# common_board_smd.net
KiCad netlist of a schematic drawn in EAGLE
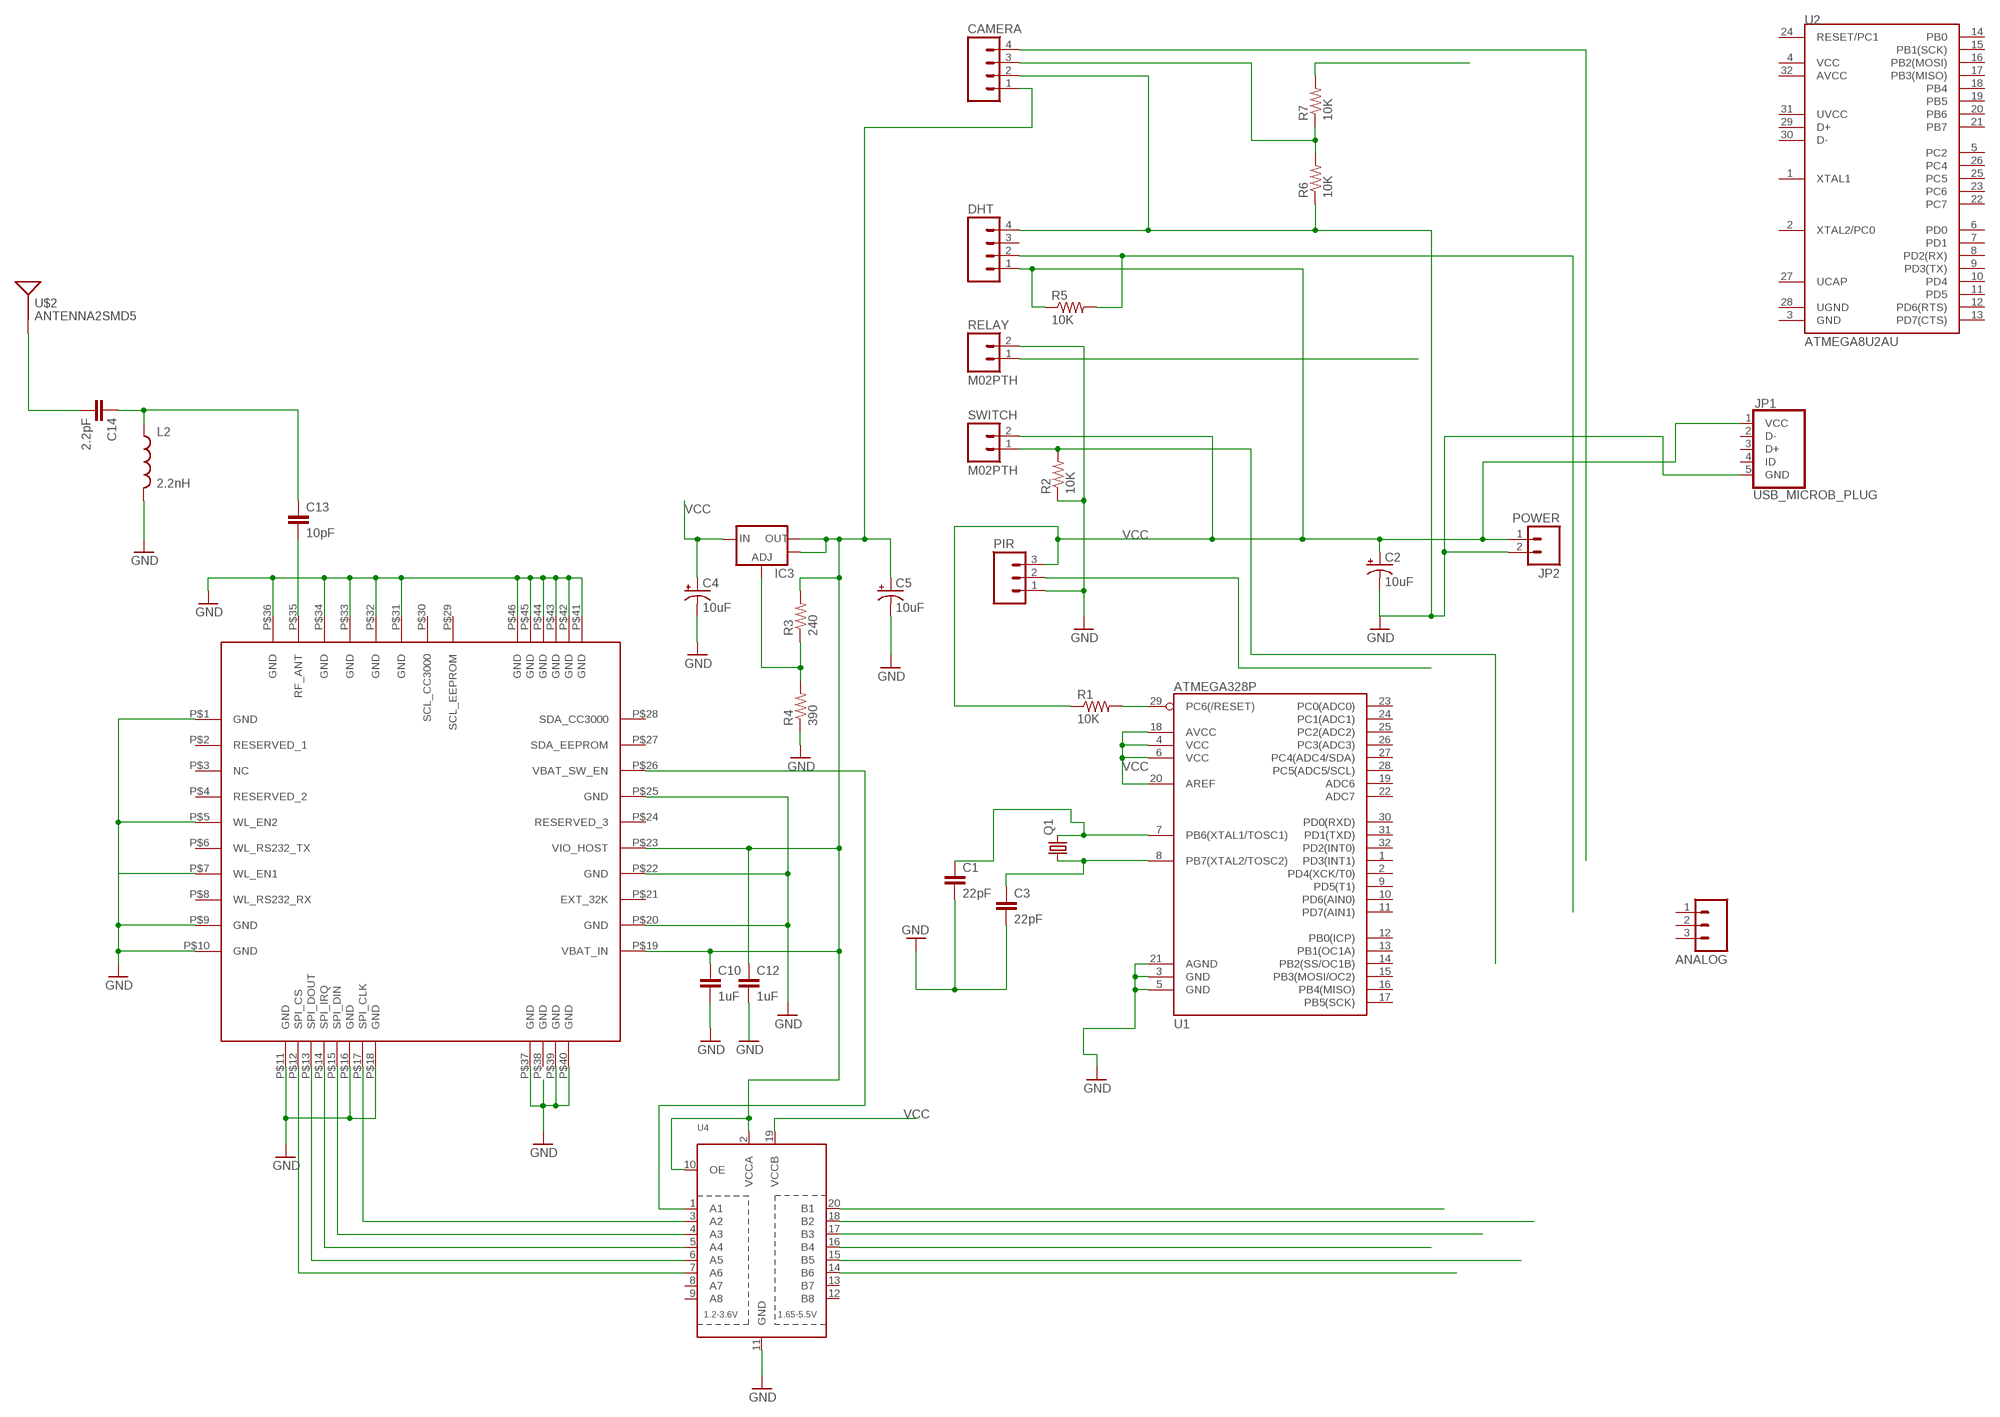
[diagram p0: schematic, sheet 1]

(export (version "E")
  (design (tool "Eeschema 10.0.6"))
  (components
    (comp (ref "ANALOG")
      (value "M03PTH")
      (footprint "eagle-import:1X03")
      (libsource (lib "eagle-import") (part "M03PTH"))
    )
    (comp (ref "C1")
      (value "22pF")
      (footprint "eagle-import:0805")
      (libsource (lib "eagle-import") (part "SparkFun-Passives_CAP0805"))
    )
    (comp (ref "C2")
      (value "10uF")
      (footprint "eagle-import:EIA3216")
      (libsource (lib "eagle-import") (part "CAP_POL1206"))
    )
    (comp (ref "C3")
      (value "22pF")
      (footprint "eagle-import:0805")
      (libsource (lib "eagle-import") (part "SparkFun-Passives_CAP0805"))
    )
    (comp (ref "C4")
      (value "10uF")
      (footprint "eagle-import:EIA3528")
      (libsource (lib "eagle-import") (part "CAP_POL3528"))
    )
    (comp (ref "C5")
      (value "10uF")
      (footprint "eagle-import:EIA3528")
      (libsource (lib "eagle-import") (part "CAP_POL3528"))
    )
    (comp (ref "C10")
      (value "1uF")
      (footprint "eagle-import:1206")
      (libsource (lib "eagle-import") (part "CAP1206"))
    )
    (comp (ref "C12")
      (value "1uF")
      (footprint "eagle-import:1206")
      (libsource (lib "eagle-import") (part "CAP1206"))
    )
    (comp (ref "C13")
      (value "10pF")
      (footprint "eagle-import:0805")
      (libsource (lib "eagle-import") (part "CAP0805"))
    )
    (comp (ref "C14")
      (value "2.2pF")
      (footprint "eagle-import:0805")
      (libsource (lib "eagle-import") (part "CAP0805"))
    )
    (comp (ref "CAMERA")
      (value "M04PTH")
      (footprint "eagle-import:1X04")
      (libsource (lib "eagle-import") (part "M04PTH"))
    )
    (comp (ref "DHT")
      (value "M04PTH")
      (footprint "eagle-import:1X04")
      (libsource (lib "eagle-import") (part "M04PTH"))
    )
    (comp (ref "IC3")
      (value "V_REG_LM1117SOT223")
      (footprint "eagle-import:SOT223")
      (libsource (lib "eagle-import") (part "V_REG_LM1117SOT223"))
    )
    (comp (ref "JP1")
      (value "USB_MICROB_PLUG")
      (footprint "eagle-import:MICRO-B-RA-SMT")
      (libsource (lib "eagle-import") (part "USB_MICROB_PLUG"))
    )
    (comp (ref "JP2")
      (value "POWER")
      (footprint "eagle-import:1X02")
      (libsource (lib "eagle-import") (part "M02PTH"))
    )
    (comp (ref "L2")
      (value "2.2nH")
      (footprint "eagle-import:0805")
      (libsource (lib "eagle-import") (part "INDUCTOR0805"))
    )
    (comp (ref "PIR")
      (value "M03PTH")
      (footprint "eagle-import:1X03")
      (libsource (lib "eagle-import") (part "M03PTH"))
    )
    (comp (ref "Q1")
      (value "CRYSTALHC49U-V")
      (footprint "eagle-import:HC49U-V")
      (libsource (lib "eagle-import") (part "CRYSTALHC49U-V"))
    )
    (comp (ref "R1")
      (value "10K")
      (footprint "eagle-import:0805")
      (libsource (lib "eagle-import") (part "RESISTOR0805-RES"))
    )
    (comp (ref "R2")
      (value "10K")
      (footprint "eagle-import:0805")
      (libsource (lib "eagle-import") (part "RESISTOR0805-RES"))
    )
    (comp (ref "R3")
      (value "240")
      (footprint "eagle-import:0805")
      (libsource (lib "eagle-import") (part "SparkFun-Resistors_RESISTOR0805-RES"))
    )
    (comp (ref "R4")
      (value "390")
      (footprint "eagle-import:0805")
      (libsource (lib "eagle-import") (part "SparkFun-Resistors_RESISTOR0805-RES"))
    )
    (comp (ref "R5")
      (value "10K")
      (footprint "eagle-import:0805")
      (libsource (lib "eagle-import") (part "RESISTOR0805-RES"))
    )
    (comp (ref "R6")
      (value "10K")
      (footprint "eagle-import:0805")
      (libsource (lib "eagle-import") (part "RESISTOR0805-RES"))
    )
    (comp (ref "R7")
      (value "10K")
      (footprint "eagle-import:0805")
      (libsource (lib "eagle-import") (part "RESISTOR0805-RES"))
    )
    (comp (ref "RELAY")
      (value "M02PTH")
      (footprint "eagle-import:1X02")
      (libsource (lib "eagle-import") (part "M02PTH"))
    )
    (comp (ref "SWITCH")
      (value "M02PTH")
      (footprint "eagle-import:1X02")
      (libsource (lib "eagle-import") (part "M02PTH"))
    )
    (comp (ref "U$1")
      (value "CC3000")
      (footprint "eagle-import:CC3000")
      (fields (field (name "AUTHOR") "Matt Bigarani"))
      (libsource (lib "eagle-import") (part "CC3000"))
    )
    (comp (ref "U$2")
      (value "ANTENNA2SMD5")
      (footprint "eagle-import:ANTENNA-CHIP5")
      (libsource (lib "eagle-import") (part "ANTENNA2SMD5"))
    )
    (comp (ref "U1")
      (value "ATMEGA328P")
      (footprint "eagle-import:TQFP32-08")
      (libsource (lib "eagle-import") (part "ATMEGA328_SMT"))
    )
    (comp (ref "U2")
      (value "ATMEGA8U2AU")
      (footprint "eagle-import:TQFP32-08")
      (libsource (lib "eagle-import") (part "ATMEGA8U2AU"))
    )
    (comp (ref "U4")
      (value "TXB0108PWR")
      (footprint "eagle-import:TSSOP20")
      (libsource (lib "eagle-import") (part "TXB0108PWR"))
    )
  )
  (nets
    (net (code "1") (name "/SCL_CC3000") (class "Default")
      (node (ref "U$1") (pin "P$30") (pinfunction "SCL_CC3000_P$30") (pintype "power_in"))
    )
    (net (code "2") (name "/SCL_EEPROM") (class "Default")
      (node (ref "U$1") (pin "P$29") (pinfunction "SCL_EEPROM_P$29") (pintype "power_in"))
    )
    (net (code "3") (name "/VCC") (class "Default")
      (node (ref "C2") (pin "A") (pinfunction "+_A") (pintype "passive"))
      (node (ref "C4") (pin "A") (pinfunction "+_A") (pintype "passive"))
      (node (ref "DHT") (pin "1") (pinfunction "1_1") (pintype "passive"))
      (node (ref "IC3") (pin "3") (pinfunction "IN_3") (pintype "input"))
      (node (ref "JP1") (pin "1") (pinfunction "VCC_1") (pintype "bidirectional"))
      (node (ref "JP2") (pin "1") (pinfunction "1_1") (pintype "passive"))
      (node (ref "PIR") (pin "3") (pinfunction "3_3") (pintype "passive"))
      (node (ref "R1") (pin "1") (pinfunction "1_1") (pintype "passive"))
      (node (ref "R5") (pin "1") (pinfunction "1_1") (pintype "passive"))
      (node (ref "SWITCH") (pin "2") (pinfunction "2_2") (pintype "passive"))
      (node (ref "U1") (pin "18") (pinfunction "AVCC_18") (pintype "bidirectional"))
      (node (ref "U1") (pin "20") (pinfunction "AREF_20") (pintype "bidirectional"))
      (node (ref "U1") (pin "4") (pinfunction "VCC_4") (pintype "bidirectional"))
      (node (ref "U1") (pin "6") (pinfunction "VCC_6") (pintype "bidirectional"))
      (node (ref "U4") (pin "19") (pinfunction "VCCB_19") (pintype "bidirectional"))
    )
    (net (code "4") (name "GND") (class "Default")
      (node (ref "C1") (pin "2") (pinfunction "2_2") (pintype "passive"))
      (node (ref "C10") (pin "2") (pinfunction "2_2") (pintype "passive"))
      (node (ref "C2") (pin "C") (pinfunction "-_C") (pintype "passive"))
      (node (ref "C3") (pin "2") (pinfunction "2_2") (pintype "passive"))
      (node (ref "C4") (pin "C") (pinfunction "-_C") (pintype "passive"))
      (node (ref "C5") (pin "C") (pinfunction "-_C") (pintype "passive"))
      (node (ref "CAMERA") (pin "2") (pinfunction "2_2") (pintype "passive"))
      (node (ref "DHT") (pin "4") (pinfunction "4_4") (pintype "passive"))
      (node (ref "JP1") (pin "5") (pinfunction "GND_5") (pintype "bidirectional"))
      (node (ref "JP2") (pin "2") (pinfunction "2_2") (pintype "passive"))
      (node (ref "L2") (pin "2") (pinfunction "2_2") (pintype "passive"))
      (node (ref "PIR") (pin "1") (pinfunction "1_1") (pintype "passive"))
      (node (ref "R2") (pin "1") (pinfunction "1_1") (pintype "passive"))
      (node (ref "R4") (pin "1") (pinfunction "1_1") (pintype "passive"))
      (node (ref "R6") (pin "1") (pinfunction "1_1") (pintype "passive"))
      (node (ref "RELAY") (pin "2") (pinfunction "2_2") (pintype "passive"))
      (node (ref "U$1") (pin "P$1") (pinfunction "GND_P$1") (pintype "power_in"))
      (node (ref "U$1") (pin "P$10") (pinfunction "GND_P$10") (pintype "power_in"))
      (node (ref "U$1") (pin "P$11") (pinfunction "GND_P$11") (pintype "power_in"))
      (node (ref "U$1") (pin "P$16") (pinfunction "GND_P$16") (pintype "power_in"))
      (node (ref "U$1") (pin "P$18") (pinfunction "GND_P$18") (pintype "power_in"))
      (node (ref "U$1") (pin "P$20") (pinfunction "GND_P$20") (pintype "bidirectional"))
      (node (ref "U$1") (pin "P$22") (pinfunction "GND_P$22") (pintype "bidirectional"))
      (node (ref "U$1") (pin "P$25") (pinfunction "GND_P$25") (pintype "bidirectional"))
      (node (ref "U$1") (pin "P$31") (pinfunction "GND_P$31") (pintype "power_in"))
      (node (ref "U$1") (pin "P$32") (pinfunction "GND_P$32") (pintype "power_in"))
      (node (ref "U$1") (pin "P$33") (pinfunction "GND_P$33") (pintype "power_in"))
      (node (ref "U$1") (pin "P$34") (pinfunction "GND_P$34") (pintype "power_in"))
      (node (ref "U$1") (pin "P$36") (pinfunction "GND_P$36") (pintype "passive"))
      (node (ref "U$1") (pin "P$37") (pinfunction "GND_P$37") (pintype "power_in"))
      (node (ref "U$1") (pin "P$39") (pinfunction "GND_P$39") (pintype "power_in"))
      (node (ref "U$1") (pin "P$40") (pinfunction "GND_P$40") (pintype "power_in"))
      (node (ref "U$1") (pin "P$41") (pinfunction "GND_P$41") (pintype "power_in"))
      (node (ref "U$1") (pin "P$42") (pinfunction "GND_P$42") (pintype "power_in"))
      (node (ref "U$1") (pin "P$43") (pinfunction "GND_P$43") (pintype "power_in"))
      (node (ref "U$1") (pin "P$44") (pinfunction "GND_P$44") (pintype "power_in"))
      (node (ref "U$1") (pin "P$45") (pinfunction "GND_P$45") (pintype "power_in"))
      (node (ref "U$1") (pin "P$46") (pinfunction "GND_P$46") (pintype "power_in"))
      (node (ref "U$1") (pin "P$5") (pinfunction "WL_EN2_P$5") (pintype "bidirectional"))
      (node (ref "U$1") (pin "P$7") (pinfunction "WL_EN1_P$7") (pintype "bidirectional"))
      (node (ref "U$1") (pin "P$9") (pinfunction "GND_P$9") (pintype "bidirectional"))
      (node (ref "U1") (pin "21") (pinfunction "AGND_21") (pintype "bidirectional"))
      (node (ref "U1") (pin "3") (pinfunction "GND_3") (pintype "bidirectional"))
      (node (ref "U1") (pin "5") (pinfunction "GND_5") (pintype "bidirectional"))
      (node (ref "U4") (pin "11") (pinfunction "GND_11") (pintype "bidirectional"))
    )
    (net (code "5") (name "Net-(C5-+)") (class "Default")
      (node (ref "C10") (pin "1") (pinfunction "1_1") (pintype "passive"))
      (node (ref "C12") (pin "1") (pinfunction "1_1") (pintype "passive"))
      (node (ref "C5") (pin "A") (pinfunction "+_A") (pintype "passive"))
      (node (ref "CAMERA") (pin "1") (pinfunction "1_1") (pintype "passive"))
      (node (ref "IC3") (pin "2") (pinfunction "OUT_2") (pintype "output"))
      (node (ref "IC3") (pin "4") (pinfunction "OUT_4") (pintype "output"))
      (node (ref "R3") (pin "2") (pinfunction "2_2") (pintype "passive"))
      (node (ref "U$1") (pin "P$19") (pinfunction "VBAT_IN_P$19") (pintype "bidirectional"))
      (node (ref "U$1") (pin "P$23") (pinfunction "VIO_HOST_P$23") (pintype "bidirectional"))
      (node (ref "U4") (pin "10") (pinfunction "OE_10") (pintype "bidirectional"))
      (node (ref "U4") (pin "2") (pinfunction "VCCA_2") (pintype "bidirectional"))
    )
    (net (code "6") (name "Net-(C13-Pad1)") (class "Default")
      (node (ref "C13") (pin "1") (pinfunction "1_1") (pintype "passive"))
      (node (ref "C14") (pin "1") (pinfunction "1_1") (pintype "passive"))
      (node (ref "L2") (pin "1") (pinfunction "1_1") (pintype "passive"))
    )
    (net (code "7") (name "Net-(CAMERA-Pad3)") (class "Default")
      (node (ref "CAMERA") (pin "3") (pinfunction "3_3") (pintype "passive"))
      (node (ref "R6") (pin "2") (pinfunction "2_2") (pintype "passive"))
      (node (ref "R7") (pin "1") (pinfunction "1_1") (pintype "passive"))
    )
    (net (code "8") (name "Net-(DHT-Pad2)") (class "Default")
      (node (ref "DHT") (pin "2") (pinfunction "2_2") (pintype "passive"))
      (node (ref "R5") (pin "2") (pinfunction "2_2") (pintype "passive"))
    )
    (net (code "9") (name "Net-(IC3-ADJ)") (class "Default")
      (node (ref "IC3") (pin "1") (pinfunction "ADJ_1") (pintype "input"))
      (node (ref "R3") (pin "1") (pinfunction "1_1") (pintype "passive"))
      (node (ref "R4") (pin "2") (pinfunction "2_2") (pintype "passive"))
    )
    (net (code "10") (name "Net-(R2-Pad2)") (class "Default")
      (node (ref "R2") (pin "2") (pinfunction "2_2") (pintype "passive"))
      (node (ref "SWITCH") (pin "1") (pinfunction "1_1") (pintype "passive"))
    )
    (net (code "11") (name "Net-(U$1-RF_ANT)") (class "Default")
      (node (ref "C13") (pin "2") (pinfunction "2_2") (pintype "passive"))
      (node (ref "U$1") (pin "P$35") (pinfunction "RF_ANT_P$35") (pintype "bidirectional"))
    )
    (net (code "12") (name "Net-(U$1-SPI_CLK)") (class "Default")
      (node (ref "U$1") (pin "P$17") (pinfunction "SPI_CLK_P$17") (pintype "bidirectional"))
      (node (ref "U4") (pin "3") (pinfunction "A2_3") (pintype "bidirectional"))
    )
    (net (code "13") (name "Net-(U$1-SPI_CS)") (class "Default")
      (node (ref "U$1") (pin "P$12") (pinfunction "SPI_CS_P$12") (pintype "bidirectional"))
      (node (ref "U4") (pin "7") (pinfunction "A6_7") (pintype "bidirectional"))
    )
    (net (code "14") (name "Net-(U$1-SPI_DIN)") (class "Default")
      (node (ref "U$1") (pin "P$15") (pinfunction "SPI_DIN_P$15") (pintype "bidirectional"))
      (node (ref "U4") (pin "4") (pinfunction "A3_4") (pintype "bidirectional"))
    )
    (net (code "15") (name "Net-(U$1-SPI_DOUT)") (class "Default")
      (node (ref "U$1") (pin "P$13") (pinfunction "SPI_DOUT_P$13") (pintype "bidirectional"))
      (node (ref "U4") (pin "6") (pinfunction "A5_6") (pintype "bidirectional"))
    )
    (net (code "16") (name "Net-(U$1-SPI_IRQ)") (class "Default")
      (node (ref "U$1") (pin "P$14") (pinfunction "SPI_IRQ_P$14") (pintype "bidirectional"))
      (node (ref "U4") (pin "5") (pinfunction "A4_5") (pintype "bidirectional"))
    )
    (net (code "17") (name "Net-(U$1-VBAT_SW_EN)") (class "Default")
      (node (ref "U$1") (pin "P$26") (pinfunction "VBAT_SW_EN_P$26") (pintype "bidirectional"))
      (node (ref "U4") (pin "1") (pinfunction "A1_1") (pintype "bidirectional"))
    )
    (net (code "18") (name "Net-(U$2-SIGNAL)") (class "Default")
      (node (ref "C14") (pin "2") (pinfunction "2_2") (pintype "passive"))
      (node (ref "U$2") (pin "FEED") (pinfunction "SIGNAL_FEED") (pintype "bidirectional"))
    )
    (net (code "19") (name "Net-(U1-PB6(XTAL1{slash}TOSC1))") (class "Default")
      (node (ref "C1") (pin "1") (pinfunction "1_1") (pintype "passive"))
      (node (ref "Q1") (pin "2") (pinfunction "2_2") (pintype "passive"))
      (node (ref "U1") (pin "7") (pinfunction "PB6(XTAL1/TOSC1)_7") (pintype "bidirectional"))
    )
    (net (code "20") (name "Net-(U1-PB7(XTAL2{slash}TOSC2))") (class "Default")
      (node (ref "C3") (pin "1") (pinfunction "1_1") (pintype "passive"))
      (node (ref "Q1") (pin "1") (pinfunction "1_1") (pintype "passive"))
      (node (ref "U1") (pin "8") (pinfunction "PB7(XTAL2/TOSC2)_8") (pintype "bidirectional"))
    )
    (net (code "21") (name "Net-(U1-PC6({slash}RESET))") (class "Default")
      (node (ref "R1") (pin "2") (pinfunction "2_2") (pintype "passive"))
      (node (ref "U1") (pin "29") (pinfunction "PC6(/RESET)_29") (pintype "bidirectional"))
    )
    (net (code "22") (name "unconnected-(ANALOG-Pad1)") (class "Default")
      (node (ref "ANALOG") (pin "1") (pinfunction "1_1") (pintype "passive"))
    )
    (net (code "23") (name "unconnected-(ANALOG-Pad2)") (class "Default")
      (node (ref "ANALOG") (pin "2") (pinfunction "2_2") (pintype "passive"))
    )
    (net (code "24") (name "unconnected-(ANALOG-Pad3)") (class "Default")
      (node (ref "ANALOG") (pin "3") (pinfunction "3_3") (pintype "passive"))
    )
    (net (code "25") (name "unconnected-(C12-Pad2)") (class "Default")
      (node (ref "C12") (pin "2") (pinfunction "2_2") (pintype "passive"))
    )
    (net (code "26") (name "unconnected-(CAMERA-Pad4)") (class "Default")
      (node (ref "CAMERA") (pin "4") (pinfunction "4_4") (pintype "passive"))
    )
    (net (code "27") (name "unconnected-(DHT-Pad3)") (class "Default")
      (node (ref "DHT") (pin "3") (pinfunction "3_3") (pintype "passive"))
    )
    (net (code "28") (name "unconnected-(JP1-D+-Pad3)") (class "Default")
      (node (ref "JP1") (pin "3") (pinfunction "D+_3") (pintype "bidirectional"))
    )
    (net (code "29") (name "unconnected-(JP1-D--Pad2)") (class "Default")
      (node (ref "JP1") (pin "2") (pinfunction "D-_2") (pintype "bidirectional"))
    )
    (net (code "30") (name "unconnected-(JP1-ID-Pad4)") (class "Default")
      (node (ref "JP1") (pin "4") (pinfunction "ID_4") (pintype "bidirectional"))
    )
    (net (code "31") (name "unconnected-(PIR-Pad2)") (class "Default")
      (node (ref "PIR") (pin "2") (pinfunction "2_2") (pintype "passive"))
    )
    (net (code "32") (name "unconnected-(R7-Pad2)") (class "Default")
      (node (ref "R7") (pin "2") (pinfunction "2_2") (pintype "passive"))
    )
    (net (code "33") (name "unconnected-(RELAY-Pad1)") (class "Default")
      (node (ref "RELAY") (pin "1") (pinfunction "1_1") (pintype "passive"))
    )
    (net (code "34") (name "unconnected-(U$1-EXT_32K-PadP$21)") (class "Default")
      (node (ref "U$1") (pin "P$21") (pinfunction "EXT_32K_P$21") (pintype "bidirectional"))
    )
    (net (code "35") (name "unconnected-(U$1-GND-PadP$38)") (class "Default")
      (node (ref "U$1") (pin "P$38") (pinfunction "GND_P$38") (pintype "passive"))
    )
    (net (code "36") (name "unconnected-(U$1-NC-PadP$3)") (class "Default")
      (node (ref "U$1") (pin "P$3") (pinfunction "NC_P$3") (pintype "no_connect"))
    )
    (net (code "37") (name "unconnected-(U$1-RESERVED_1-PadP$2)") (class "Default")
      (node (ref "U$1") (pin "P$2") (pinfunction "RESERVED_1_P$2") (pintype "bidirectional"))
    )
    (net (code "38") (name "unconnected-(U$1-RESERVED_2-PadP$4)") (class "Default")
      (node (ref "U$1") (pin "P$4") (pinfunction "RESERVED_2_P$4") (pintype "bidirectional"))
    )
    (net (code "39") (name "unconnected-(U$1-RESERVED_3-PadP$24)") (class "Default")
      (node (ref "U$1") (pin "P$24") (pinfunction "RESERVED_3_P$24") (pintype "bidirectional"))
    )
    (net (code "40") (name "unconnected-(U$1-SDA_CC3000-PadP$28)") (class "Default")
      (node (ref "U$1") (pin "P$28") (pinfunction "SDA_CC3000_P$28") (pintype "bidirectional"))
    )
    (net (code "41") (name "unconnected-(U$1-SDA_EEPROM-PadP$27)") (class "Default")
      (node (ref "U$1") (pin "P$27") (pinfunction "SDA_EEPROM_P$27") (pintype "bidirectional"))
    )
    (net (code "42") (name "unconnected-(U$1-WL_RS232_RX-PadP$8)") (class "Default")
      (node (ref "U$1") (pin "P$8") (pinfunction "WL_RS232_RX_P$8") (pintype "bidirectional"))
    )
    (net (code "43") (name "unconnected-(U$1-WL_RS232_TX-PadP$6)") (class "Default")
      (node (ref "U$1") (pin "P$6") (pinfunction "WL_RS232_TX_P$6") (pintype "bidirectional"))
    )
    (net (code "44") (name "unconnected-(U1-ADC6-Pad19)") (class "Default")
      (node (ref "U1") (pin "19") (pinfunction "ADC6_19") (pintype "bidirectional"))
    )
    (net (code "45") (name "unconnected-(U1-ADC7-Pad22)") (class "Default")
      (node (ref "U1") (pin "22") (pinfunction "ADC7_22") (pintype "bidirectional"))
    )
    (net (code "46") (name "unconnected-(U1-PB0(ICP)-Pad12)") (class "Default")
      (node (ref "U1") (pin "12") (pinfunction "PB0(ICP)_12") (pintype "bidirectional"))
    )
    (net (code "47") (name "unconnected-(U1-PB1(OC1A)-Pad13)") (class "Default")
      (node (ref "U1") (pin "13") (pinfunction "PB1(OC1A)_13") (pintype "bidirectional"))
    )
    (net (code "48") (name "unconnected-(U1-PB2(SS{slash}OC1B)-Pad14)") (class "Default")
      (node (ref "U1") (pin "14") (pinfunction "PB2(SS/OC1B)_14") (pintype "bidirectional"))
    )
    (net (code "49") (name "unconnected-(U1-PB3(MOSI{slash}OC2)-Pad15)") (class "Default")
      (node (ref "U1") (pin "15") (pinfunction "PB3(MOSI/OC2)_15") (pintype "bidirectional"))
    )
    (net (code "50") (name "unconnected-(U1-PB4(MISO)-Pad16)") (class "Default")
      (node (ref "U1") (pin "16") (pinfunction "PB4(MISO)_16") (pintype "bidirectional"))
    )
    (net (code "51") (name "unconnected-(U1-PB5(SCK)-Pad17)") (class "Default")
      (node (ref "U1") (pin "17") (pinfunction "PB5(SCK)_17") (pintype "bidirectional"))
    )
    (net (code "52") (name "unconnected-(U1-PC0(ADC0)-Pad23)") (class "Default")
      (node (ref "U1") (pin "23") (pinfunction "PC0(ADC0)_23") (pintype "bidirectional"))
    )
    (net (code "53") (name "unconnected-(U1-PC1(ADC1)-Pad24)") (class "Default")
      (node (ref "U1") (pin "24") (pinfunction "PC1(ADC1)_24") (pintype "bidirectional"))
    )
    (net (code "54") (name "unconnected-(U1-PC2(ADC2)-Pad25)") (class "Default")
      (node (ref "U1") (pin "25") (pinfunction "PC2(ADC2)_25") (pintype "bidirectional"))
    )
    (net (code "55") (name "unconnected-(U1-PC3(ADC3)-Pad26)") (class "Default")
      (node (ref "U1") (pin "26") (pinfunction "PC3(ADC3)_26") (pintype "bidirectional"))
    )
    (net (code "56") (name "unconnected-(U1-PC4(ADC4{slash}SDA)-Pad27)") (class "Default")
      (node (ref "U1") (pin "27") (pinfunction "PC4(ADC4/SDA)_27") (pintype "bidirectional"))
    )
    (net (code "57") (name "unconnected-(U1-PC5(ADC5{slash}SCL)-Pad28)") (class "Default")
      (node (ref "U1") (pin "28") (pinfunction "PC5(ADC5/SCL)_28") (pintype "bidirectional"))
    )
    (net (code "58") (name "unconnected-(U1-PD0(RXD)-Pad30)") (class "Default")
      (node (ref "U1") (pin "30") (pinfunction "PD0(RXD)_30") (pintype "bidirectional"))
    )
    (net (code "59") (name "unconnected-(U1-PD1(TXD)-Pad31)") (class "Default")
      (node (ref "U1") (pin "31") (pinfunction "PD1(TXD)_31") (pintype "bidirectional"))
    )
    (net (code "60") (name "unconnected-(U1-PD2(INT0)-Pad32)") (class "Default")
      (node (ref "U1") (pin "32") (pinfunction "PD2(INT0)_32") (pintype "bidirectional"))
    )
    (net (code "61") (name "unconnected-(U1-PD3(INT1)-Pad1)") (class "Default")
      (node (ref "U1") (pin "1") (pinfunction "PD3(INT1)_1") (pintype "bidirectional"))
    )
    (net (code "62") (name "unconnected-(U1-PD4(XCK{slash}T0)-Pad2)") (class "Default")
      (node (ref "U1") (pin "2") (pinfunction "PD4(XCK/T0)_2") (pintype "bidirectional"))
    )
    (net (code "63") (name "unconnected-(U1-PD5(T1)-Pad9)") (class "Default")
      (node (ref "U1") (pin "9") (pinfunction "PD5(T1)_9") (pintype "bidirectional"))
    )
    (net (code "64") (name "unconnected-(U1-PD6(AIN0)-Pad10)") (class "Default")
      (node (ref "U1") (pin "10") (pinfunction "PD6(AIN0)_10") (pintype "bidirectional"))
    )
    (net (code "65") (name "unconnected-(U1-PD7(AIN1)-Pad11)") (class "Default")
      (node (ref "U1") (pin "11") (pinfunction "PD7(AIN1)_11") (pintype "bidirectional"))
    )
    (net (code "66") (name "unconnected-(U2-AVCC-Pad32)") (class "Default")
      (node (ref "U2") (pin "32") (pinfunction "AVCC_32") (pintype "bidirectional"))
    )
    (net (code "67") (name "unconnected-(U2-D+-Pad29)") (class "Default")
      (node (ref "U2") (pin "29") (pinfunction "D+_29") (pintype "bidirectional"))
    )
    (net (code "68") (name "unconnected-(U2-D--Pad30)") (class "Default")
      (node (ref "U2") (pin "30") (pinfunction "D-_30") (pintype "bidirectional"))
    )
    (net (code "69") (name "unconnected-(U2-GND-Pad3)") (class "Default")
      (node (ref "U2") (pin "3") (pinfunction "GND_3") (pintype "bidirectional"))
    )
    (net (code "70") (name "unconnected-(U2-PB0-Pad14)") (class "Default")
      (node (ref "U2") (pin "14") (pinfunction "PB0_14") (pintype "bidirectional"))
    )
    (net (code "71") (name "unconnected-(U2-PB1(SCK)-Pad15)") (class "Default")
      (node (ref "U2") (pin "15") (pinfunction "PB1(SCK)_15") (pintype "bidirectional"))
    )
    (net (code "72") (name "unconnected-(U2-PB2(MOSI)-Pad16)") (class "Default")
      (node (ref "U2") (pin "16") (pinfunction "PB2(MOSI)_16") (pintype "bidirectional"))
    )
    (net (code "73") (name "unconnected-(U2-PB3(MISO)-Pad17)") (class "Default")
      (node (ref "U2") (pin "17") (pinfunction "PB3(MISO)_17") (pintype "bidirectional"))
    )
    (net (code "74") (name "unconnected-(U2-PB4-Pad18)") (class "Default")
      (node (ref "U2") (pin "18") (pinfunction "PB4_18") (pintype "bidirectional"))
    )
    (net (code "75") (name "unconnected-(U2-PB5-Pad19)") (class "Default")
      (node (ref "U2") (pin "19") (pinfunction "PB5_19") (pintype "bidirectional"))
    )
    (net (code "76") (name "unconnected-(U2-PB6-Pad20)") (class "Default")
      (node (ref "U2") (pin "20") (pinfunction "PB6_20") (pintype "bidirectional"))
    )
    (net (code "77") (name "unconnected-(U2-PB7-Pad21)") (class "Default")
      (node (ref "U2") (pin "21") (pinfunction "PB7_21") (pintype "bidirectional"))
    )
    (net (code "78") (name "unconnected-(U2-PC2-Pad5)") (class "Default")
      (node (ref "U2") (pin "5") (pinfunction "PC2_5") (pintype "bidirectional"))
    )
    (net (code "79") (name "unconnected-(U2-PC4-Pad26)") (class "Default")
      (node (ref "U2") (pin "26") (pinfunction "PC4_26") (pintype "bidirectional"))
    )
    (net (code "80") (name "unconnected-(U2-PC5-Pad25)") (class "Default")
      (node (ref "U2") (pin "25") (pinfunction "PC5_25") (pintype "bidirectional"))
    )
    (net (code "81") (name "unconnected-(U2-PC6-Pad23)") (class "Default")
      (node (ref "U2") (pin "23") (pinfunction "PC6_23") (pintype "bidirectional"))
    )
    (net (code "82") (name "unconnected-(U2-PC7-Pad22)") (class "Default")
      (node (ref "U2") (pin "22") (pinfunction "PC7_22") (pintype "bidirectional"))
    )
    (net (code "83") (name "unconnected-(U2-PD0-Pad6)") (class "Default")
      (node (ref "U2") (pin "6") (pinfunction "PD0_6") (pintype "bidirectional"))
    )
    (net (code "84") (name "unconnected-(U2-PD1-Pad7)") (class "Default")
      (node (ref "U2") (pin "7") (pinfunction "PD1_7") (pintype "bidirectional"))
    )
    (net (code "85") (name "unconnected-(U2-PD2(RX)-Pad8)") (class "Default")
      (node (ref "U2") (pin "8") (pinfunction "PD2(RX)_8") (pintype "bidirectional"))
    )
    (net (code "86") (name "unconnected-(U2-PD3(TX)-Pad9)") (class "Default")
      (node (ref "U2") (pin "9") (pinfunction "PD3(TX)_9") (pintype "bidirectional"))
    )
    (net (code "87") (name "unconnected-(U2-PD4-Pad10)") (class "Default")
      (node (ref "U2") (pin "10") (pinfunction "PD4_10") (pintype "bidirectional"))
    )
    (net (code "88") (name "unconnected-(U2-PD5-Pad11)") (class "Default")
      (node (ref "U2") (pin "11") (pinfunction "PD5_11") (pintype "bidirectional"))
    )
    (net (code "89") (name "unconnected-(U2-PD6(RTS)-Pad12)") (class "Default")
      (node (ref "U2") (pin "12") (pinfunction "PD6(RTS)_12") (pintype "bidirectional"))
    )
    (net (code "90") (name "unconnected-(U2-PD7(CTS)-Pad13)") (class "Default")
      (node (ref "U2") (pin "13") (pinfunction "PD7(CTS)_13") (pintype "bidirectional"))
    )
    (net (code "91") (name "unconnected-(U2-RESET{slash}PC1-Pad24)") (class "Default")
      (node (ref "U2") (pin "24") (pinfunction "RESET/PC1_24") (pintype "bidirectional"))
    )
    (net (code "92") (name "unconnected-(U2-UCAP-Pad27)") (class "Default")
      (node (ref "U2") (pin "27") (pinfunction "UCAP_27") (pintype "bidirectional"))
    )
    (net (code "93") (name "unconnected-(U2-UGND-Pad28)") (class "Default")
      (node (ref "U2") (pin "28") (pinfunction "UGND_28") (pintype "bidirectional"))
    )
    (net (code "94") (name "unconnected-(U2-UVCC-Pad31)") (class "Default")
      (node (ref "U2") (pin "31") (pinfunction "UVCC_31") (pintype "bidirectional"))
    )
    (net (code "95") (name "unconnected-(U2-VCC-Pad4)") (class "Default")
      (node (ref "U2") (pin "4") (pinfunction "VCC_4") (pintype "bidirectional"))
    )
    (net (code "96") (name "unconnected-(U2-XTAL1-Pad1)") (class "Default")
      (node (ref "U2") (pin "1") (pinfunction "XTAL1_1") (pintype "bidirectional"))
    )
    (net (code "97") (name "unconnected-(U2-XTAL2{slash}PC0-Pad2)") (class "Default")
      (node (ref "U2") (pin "2") (pinfunction "XTAL2/PC0_2") (pintype "bidirectional"))
    )
    (net (code "98") (name "unconnected-(U4-A7-Pad8)") (class "Default")
      (node (ref "U4") (pin "8") (pinfunction "A7_8") (pintype "bidirectional"))
    )
    (net (code "99") (name "unconnected-(U4-A8-Pad9)") (class "Default")
      (node (ref "U4") (pin "9") (pinfunction "A8_9") (pintype "bidirectional"))
    )
    (net (code "100") (name "unconnected-(U4-B1-Pad20)") (class "Default")
      (node (ref "U4") (pin "20") (pinfunction "B1_20") (pintype "bidirectional"))
    )
    (net (code "101") (name "unconnected-(U4-B2-Pad18)") (class "Default")
      (node (ref "U4") (pin "18") (pinfunction "B2_18") (pintype "bidirectional"))
    )
    (net (code "102") (name "unconnected-(U4-B3-Pad17)") (class "Default")
      (node (ref "U4") (pin "17") (pinfunction "B3_17") (pintype "bidirectional"))
    )
    (net (code "103") (name "unconnected-(U4-B4-Pad16)") (class "Default")
      (node (ref "U4") (pin "16") (pinfunction "B4_16") (pintype "bidirectional"))
    )
    (net (code "104") (name "unconnected-(U4-B5-Pad15)") (class "Default")
      (node (ref "U4") (pin "15") (pinfunction "B5_15") (pintype "bidirectional"))
    )
    (net (code "105") (name "unconnected-(U4-B6-Pad14)") (class "Default")
      (node (ref "U4") (pin "14") (pinfunction "B6_14") (pintype "bidirectional"))
    )
    (net (code "106") (name "unconnected-(U4-B7-Pad13)") (class "Default")
      (node (ref "U4") (pin "13") (pinfunction "B7_13") (pintype "bidirectional"))
    )
    (net (code "107") (name "unconnected-(U4-B8-Pad12)") (class "Default")
      (node (ref "U4") (pin "12") (pinfunction "B8_12") (pintype "bidirectional"))
    )
  )
)
